# DRV8701E.net
KiCad netlist of a schematic drawn in Altium Designer
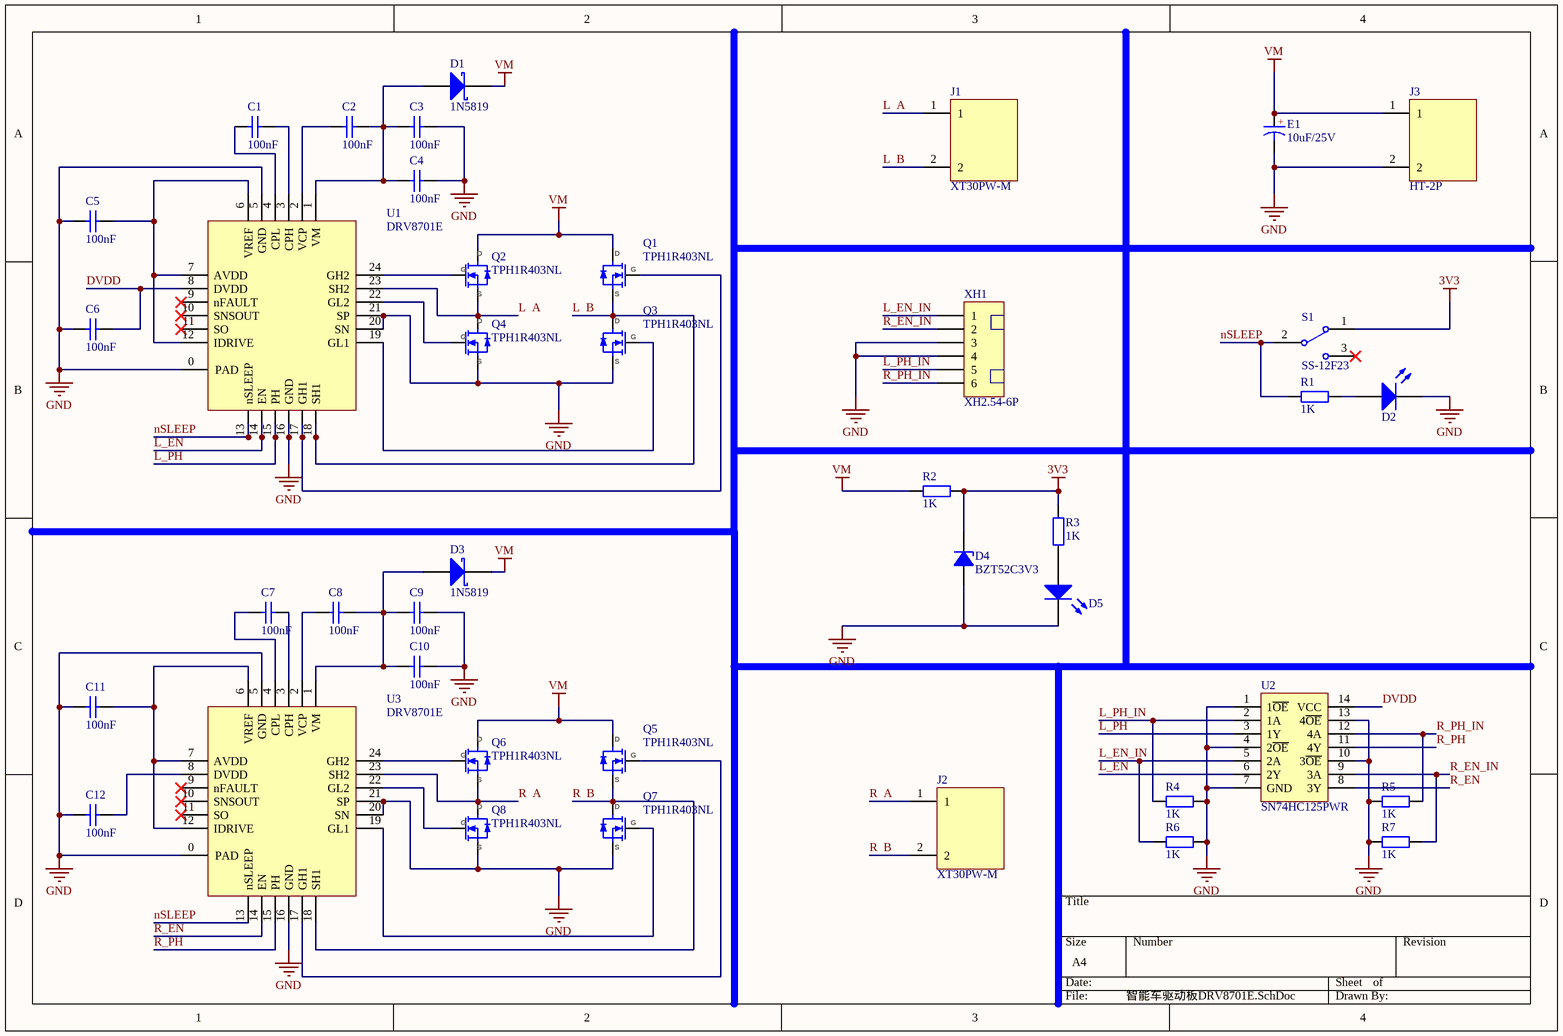
[diagram p0: 智能车驱动板DRV8701E.SchDoc]

(export (version "E")
  (design (tool "Eeschema 10.0.6"))
  (components
    (comp (ref "C1")
      (value "100nF")
      (footprint "C0603_L")
      (description "贴片电容")
      (libsource (lib "0.1_电容&电感&电阻&保险丝") (part "C-SMD"))
    )
    (comp (ref "C2")
      (value "100nF")
      (footprint "C0603_L")
      (description "贴片电容")
      (libsource (lib "0.1_电容&电感&电阻&保险丝") (part "C-SMD"))
    )
    (comp (ref "C3")
      (value "100nF")
      (footprint "C0603_L")
      (description "贴片电容")
      (libsource (lib "0.1_电容&电感&电阻&保险丝") (part "C-SMD"))
    )
    (comp (ref "C4")
      (value "100nF")
      (footprint "C0603_L")
      (description "贴片电容")
      (libsource (lib "0.1_电容&电感&电阻&保险丝") (part "C-SMD"))
    )
    (comp (ref "C5")
      (value "100nF")
      (footprint "C0603_L")
      (description "贴片电容")
      (libsource (lib "0.1_电容&电感&电阻&保险丝") (part "C-SMD"))
    )
    (comp (ref "C6")
      (value "100nF")
      (footprint "C0603_L")
      (description "贴片电容")
      (libsource (lib "0.1_电容&电感&电阻&保险丝") (part "C-SMD"))
    )
    (comp (ref "C7")
      (value "100nF")
      (footprint "C0603_L")
      (description "贴片电容")
      (libsource (lib "0.1_电容&电感&电阻&保险丝") (part "C-SMD"))
    )
    (comp (ref "C8")
      (value "100nF")
      (footprint "C0603_L")
      (description "贴片电容")
      (libsource (lib "0.1_电容&电感&电阻&保险丝") (part "C-SMD"))
    )
    (comp (ref "C9")
      (value "100nF")
      (footprint "C0603_L")
      (description "贴片电容")
      (libsource (lib "0.1_电容&电感&电阻&保险丝") (part "C-SMD"))
    )
    (comp (ref "C10")
      (value "100nF")
      (footprint "C0603_L")
      (description "贴片电容")
      (libsource (lib "0.1_电容&电感&电阻&保险丝") (part "C-SMD"))
    )
    (comp (ref "C11")
      (value "100nF")
      (footprint "C0603_L")
      (description "贴片电容")
      (libsource (lib "0.1_电容&电感&电阻&保险丝") (part "C-SMD"))
    )
    (comp (ref "C12")
      (value "100nF")
      (footprint "C0603_L")
      (description "贴片电容")
      (libsource (lib "0.1_电容&电感&电阻&保险丝") (part "C-SMD"))
    )
    (comp (ref "D1")
      (value "1N5819")
      (footprint "SOD-323")
      (description "肖特基二极管")
      (libsource (lib "0.2_二极管&整流桥") (part "1N5819"))
    )
    (comp (ref "D2")
      (value "LED")
      (footprint "LED-0603_R")
      (description "贴片发光二极管")
      (libsource (lib "0.3_LED发光二极管") (part "LED_SMD"))
    )
    (comp (ref "D3")
      (value "1N5819")
      (footprint "SOD-323")
      (description "肖特基二极管")
      (libsource (lib "0.2_二极管&整流桥") (part "1N5819"))
    )
    (comp (ref "D4")
      (value "BZT52C3V3")
      (footprint "SOD-123-L")
      (description "3.3V稳压二极管")
      (fields (field (name "PUBLISHER") "Altium Limited"))
      (libsource (lib "0.2_二极管&整流桥") (part "Diode Zen"))
    )
    (comp (ref "D5")
      (value "LED")
      (footprint "LED-0603_R")
      (description "贴片发光二极管")
      (libsource (lib "0.3_LED发光二极管") (part "LED_SMD"))
    )
    (comp (ref "E1")
      (value "10uF/25V")
      (footprint "CT-2.0*5*8-R")
      (description "直插固态电容")
      (libsource (lib "0.1_电容&电感&电阻&保险丝") (part "C-CS"))
    )
    (comp (ref "J1")
      (value "XT30PW-M")
      (footprint "XT30-WI")
      (description "30A Low Temperature Rise Fire Retardant Plug")
      (libsource (lib "5.12_XT30&XT60") (part "XT30PW-M"))
    )
    (comp (ref "J2")
      (value "XT30PW-M")
      (footprint "XT30-WI")
      (description "30A Low Temperature Rise Fire Retardant Plug")
      (libsource (lib "5.12_XT30&XT60") (part "XT30PW-M"))
    )
    (comp (ref "J3")
      (value "HT-2P")
      (footprint "CZ-5.08-L-Z-2P")
      (description "30A Low Temperature Rise Fire Retardant Plug")
      (fields (field (name "MANUFACTURER_PART_NUMBER") "XT30PW-M"))
      (libsource (lib "5.12_XT30&XT60") (part "XT30PW-M"))
    )
    (comp (ref "Q1")
      (value "TPH1R403NL")
      (footprint "DFN5x6")
      (description "N沟道MOS")
      (libsource (lib "0.4_场效应管&可控硅") (part "TPH1R403NL"))
    )
    (comp (ref "Q2")
      (value "TPH1R403NL")
      (footprint "DFN5x6")
      (description "N沟道MOS")
      (libsource (lib "0.4_场效应管&可控硅") (part "TPH1R403NL"))
    )
    (comp (ref "Q3")
      (value "TPH1R403NL")
      (footprint "DFN5x6")
      (description "N沟道MOS")
      (libsource (lib "0.4_场效应管&可控硅") (part "TPH1R403NL"))
    )
    (comp (ref "Q4")
      (value "TPH1R403NL")
      (footprint "DFN5x6")
      (description "N沟道MOS")
      (libsource (lib "0.4_场效应管&可控硅") (part "TPH1R403NL"))
    )
    (comp (ref "Q5")
      (value "TPH1R403NL")
      (footprint "DFN5x6")
      (description "N沟道MOS")
      (libsource (lib "0.4_场效应管&可控硅") (part "TPH1R403NL"))
    )
    (comp (ref "Q6")
      (value "TPH1R403NL")
      (footprint "DFN5x6")
      (description "N沟道MOS")
      (libsource (lib "0.4_场效应管&可控硅") (part "TPH1R403NL"))
    )
    (comp (ref "Q7")
      (value "TPH1R403NL")
      (footprint "DFN5x6")
      (description "N沟道MOS")
      (libsource (lib "0.4_场效应管&可控硅") (part "TPH1R403NL"))
    )
    (comp (ref "Q8")
      (value "TPH1R403NL")
      (footprint "DFN5x6")
      (description "N沟道MOS")
      (libsource (lib "0.4_场效应管&可控硅") (part "TPH1R403NL"))
    )
    (comp (ref "R1")
      (value "1K")
      (footprint "R0603_L")
      (description "贴片电阻")
      (libsource (lib "0.1_电容&电感&电阻&保险丝") (part "R-SMD"))
    )
    (comp (ref "R2")
      (value "1K")
      (footprint "R0603_L")
      (description "贴片电阻")
      (libsource (lib "0.1_电容&电感&电阻&保险丝") (part "R-SMD"))
    )
    (comp (ref "R3")
      (value "1K")
      (footprint "R0603_L")
      (description "贴片电阻")
      (libsource (lib "0.1_电容&电感&电阻&保险丝") (part "R-SMD"))
    )
    (comp (ref "R4")
      (value "1K")
      (footprint "R0603_L")
      (description "贴片电阻")
      (libsource (lib "0.1_电容&电感&电阻&保险丝") (part "R-SMD"))
    )
    (comp (ref "R5")
      (value "1K")
      (footprint "R0603_L")
      (description "贴片电阻")
      (libsource (lib "0.1_电容&电感&电阻&保险丝") (part "R-SMD"))
    )
    (comp (ref "R6")
      (value "1K")
      (footprint "R0603_L")
      (description "贴片电阻")
      (libsource (lib "0.1_电容&电感&电阻&保险丝") (part "R-SMD"))
    )
    (comp (ref "R7")
      (value "1K")
      (footprint "R0603_L")
      (description "贴片电阻")
      (libsource (lib "0.1_电容&电感&电阻&保险丝") (part "R-SMD"))
    )
    (comp (ref "S1")
      (value "SS-12F23")
      (footprint "SS-12D10")
      (description "1路波动开关")
      (libsource (lib "0.8_按键&开关") (part "SSW-1P"))
    )
    (comp (ref "U1")
      (value "DRV8701E")
      (footprint "QFN24-4x4")
      (description "DRV8701E Ti全桥驱动芯片")
      (libsource (lib "1.3_电机驱动芯片") (part "DRV8701E"))
    )
    (comp (ref "U2")
      (value "SN74HC125PWR")
      (footprint "TSSOP14")
      (description "三态输出的四路缓冲器")
      (libsource (lib "1.7_隔离类芯片") (part "SN74HC125PWR"))
    )
    (comp (ref "U3")
      (value "DRV8701E")
      (footprint "QFN24-4x4")
      (description "DRV8701E Ti全桥驱动芯片")
      (libsource (lib "1.3_电机驱动芯片") (part "DRV8701E"))
    )
    (comp (ref "XH1")
      (value "XH2.54-6P")
      (footprint "XH2.54-6P-WI")
      (libsource (lib "5.2_XH") (part "XH2.54-6P"))
    )
  )
  (nets
    (net (code "1") (name "/DVDD") (class "Default")
      (node (ref "C6") (pin "2") (pinfunction "2_2") (pintype "passive"))
      (node (ref "U1") (pin "8") (pinfunction "DVDD_8") (pintype "passive"))
      (node (ref "U2") (pin "14") (pinfunction "VCC_14") (pintype "passive"))
    )
    (net (code "2") (name "/L  A") (class "Default")
      (node (ref "J1") (pin "1") (pinfunction "1_1") (pintype "passive"))
      (node (ref "Q2") (pin "3") (pinfunction "S_3") (pintype "passive"))
      (node (ref "Q4") (pin "1") (pinfunction "D_1") (pintype "passive"))
      (node (ref "U1") (pin "23") (pinfunction "SH2_23") (pintype "passive"))
    )
    (net (code "3") (name "/L  B") (class "Default")
      (node (ref "J1") (pin "2") (pinfunction "2_2") (pintype "passive"))
      (node (ref "Q1") (pin "3") (pinfunction "S_3") (pintype "passive"))
      (node (ref "Q3") (pin "1") (pinfunction "D_1") (pintype "passive"))
      (node (ref "U1") (pin "18") (pinfunction "SH1_18") (pintype "passive"))
    )
    (net (code "4") (name "/L_EN") (class "Default")
      (node (ref "U1") (pin "14") (pinfunction "EN_14") (pintype "passive"))
      (node (ref "U2") (pin "6") (pinfunction "2Y_6") (pintype "passive"))
    )
    (net (code "5") (name "/L_EN_IN") (class "Default")
      (node (ref "R6") (pin "1") (pinfunction "1_1") (pintype "passive"))
      (node (ref "U2") (pin "5") (pinfunction "2A_5") (pintype "passive"))
      (node (ref "XH1") (pin "1") (pinfunction "1_1") (pintype "passive"))
    )
    (net (code "6") (name "/L_PH") (class "Default")
      (node (ref "U1") (pin "15") (pinfunction "PH_15") (pintype "passive"))
      (node (ref "U2") (pin "3") (pinfunction "1Y_3") (pintype "passive"))
    )
    (net (code "7") (name "/L_PH_IN") (class "Default")
      (node (ref "R4") (pin "1") (pinfunction "1_1") (pintype "passive"))
      (node (ref "U2") (pin "2") (pinfunction "1A_2") (pintype "passive"))
      (node (ref "XH1") (pin "5") (pinfunction "5_5") (pintype "passive"))
    )
    (net (code "8") (name "/R  A") (class "Default")
      (node (ref "J2") (pin "1") (pinfunction "1_1") (pintype "passive"))
      (node (ref "Q6") (pin "3") (pinfunction "S_3") (pintype "passive"))
      (node (ref "Q8") (pin "1") (pinfunction "D_1") (pintype "passive"))
      (node (ref "U3") (pin "23") (pinfunction "SH2_23") (pintype "passive"))
    )
    (net (code "9") (name "/R  B") (class "Default")
      (node (ref "J2") (pin "2") (pinfunction "2_2") (pintype "passive"))
      (node (ref "Q5") (pin "3") (pinfunction "S_3") (pintype "passive"))
      (node (ref "Q7") (pin "1") (pinfunction "D_1") (pintype "passive"))
      (node (ref "U3") (pin "18") (pinfunction "SH1_18") (pintype "passive"))
    )
    (net (code "10") (name "/R_EN") (class "Default")
      (node (ref "U2") (pin "8") (pinfunction "3Y_8") (pintype "passive"))
      (node (ref "U3") (pin "14") (pinfunction "EN_14") (pintype "passive"))
    )
    (net (code "11") (name "/R_EN_IN") (class "Default")
      (node (ref "R7") (pin "2") (pinfunction "2_2") (pintype "passive"))
      (node (ref "U2") (pin "9") (pinfunction "3A_9") (pintype "passive"))
      (node (ref "XH1") (pin "2") (pinfunction "2_2") (pintype "passive"))
    )
    (net (code "12") (name "/R_PH") (class "Default")
      (node (ref "U2") (pin "11") (pinfunction "4Y_11") (pintype "passive"))
      (node (ref "U3") (pin "15") (pinfunction "PH_15") (pintype "passive"))
    )
    (net (code "13") (name "/R_PH_IN") (class "Default")
      (node (ref "R5") (pin "2") (pinfunction "2_2") (pintype "passive"))
      (node (ref "U2") (pin "12") (pinfunction "4A_12") (pintype "passive"))
      (node (ref "XH1") (pin "6") (pinfunction "6_6") (pintype "passive"))
    )
    (net (code "14") (name "/nSLEEP") (class "Default")
      (node (ref "R1") (pin "1") (pinfunction "1_1") (pintype "passive"))
      (node (ref "S1") (pin "2") (pinfunction "2_2") (pintype "passive"))
      (node (ref "U1") (pin "13") (pinfunction "nSLEEP_13") (pintype "passive"))
      (node (ref "U3") (pin "13") (pinfunction "nSLEEP_13") (pintype "passive"))
    )
    (net (code "15") (name "3V3") (class "Default")
      (node (ref "D4") (pin "K") (pinfunction "K_K") (pintype "passive"))
      (node (ref "R2") (pin "2") (pinfunction "2_2") (pintype "passive"))
      (node (ref "R3") (pin "2") (pinfunction "2_2") (pintype "passive"))
      (node (ref "S1") (pin "1") (pinfunction "1_1") (pintype "passive"))
    )
    (net (code "16") (name "GND") (class "Default")
      (node (ref "C10") (pin "2") (pinfunction "2_2") (pintype "passive"))
      (node (ref "C11") (pin "1") (pinfunction "1_1") (pintype "passive"))
      (node (ref "C12") (pin "1") (pinfunction "1_1") (pintype "passive"))
      (node (ref "C3") (pin "2") (pinfunction "2_2") (pintype "passive"))
      (node (ref "C4") (pin "2") (pinfunction "2_2") (pintype "passive"))
      (node (ref "C5") (pin "1") (pinfunction "1_1") (pintype "passive"))
      (node (ref "C6") (pin "1") (pinfunction "1_1") (pintype "passive"))
      (node (ref "C9") (pin "2") (pinfunction "2_2") (pintype "passive"))
      (node (ref "D2") (pin "2") (pinfunction "K_2") (pintype "passive"))
      (node (ref "D4") (pin "A") (pinfunction "A_A") (pintype "passive"))
      (node (ref "D5") (pin "2") (pinfunction "K_2") (pintype "passive"))
      (node (ref "E1") (pin "2") (pinfunction "2_2") (pintype "passive"))
      (node (ref "J3") (pin "2") (pinfunction "2_2") (pintype "passive"))
      (node (ref "Q3") (pin "3") (pinfunction "S_3") (pintype "passive"))
      (node (ref "Q4") (pin "3") (pinfunction "S_3") (pintype "passive"))
      (node (ref "Q7") (pin "3") (pinfunction "S_3") (pintype "passive"))
      (node (ref "Q8") (pin "3") (pinfunction "S_3") (pintype "passive"))
      (node (ref "R4") (pin "2") (pinfunction "2_2") (pintype "passive"))
      (node (ref "R5") (pin "1") (pinfunction "1_1") (pintype "passive"))
      (node (ref "R6") (pin "2") (pinfunction "2_2") (pintype "passive"))
      (node (ref "R7") (pin "1") (pinfunction "1_1") (pintype "passive"))
      (node (ref "U1") (pin "0") (pinfunction "PAD_0") (pintype "passive"))
      (node (ref "U1") (pin "16") (pinfunction "GND_16") (pintype "passive"))
      (node (ref "U1") (pin "20") (pinfunction "SN_20") (pintype "passive"))
      (node (ref "U1") (pin "21") (pinfunction "SP_21") (pintype "passive"))
      (node (ref "U1") (pin "5") (pinfunction "GND_5") (pintype "passive"))
      (node (ref "U2") (pin "1") (pinfunction "1~{OE}_1") (pintype "passive"))
      (node (ref "U2") (pin "10") (pinfunction "3~{OE}_10") (pintype "passive"))
      (node (ref "U2") (pin "13") (pinfunction "4~{OE}_13") (pintype "passive"))
      (node (ref "U2") (pin "4") (pinfunction "2~{OE}_4") (pintype "passive"))
      (node (ref "U2") (pin "7") (pinfunction "GND_7") (pintype "passive"))
      (node (ref "U3") (pin "0") (pinfunction "PAD_0") (pintype "passive"))
      (node (ref "U3") (pin "16") (pinfunction "GND_16") (pintype "passive"))
      (node (ref "U3") (pin "20") (pinfunction "SN_20") (pintype "passive"))
      (node (ref "U3") (pin "21") (pinfunction "SP_21") (pintype "passive"))
      (node (ref "U3") (pin "5") (pinfunction "GND_5") (pintype "passive"))
      (node (ref "XH1") (pin "3") (pinfunction "3_3") (pintype "passive"))
      (node (ref "XH1") (pin "4") (pinfunction "4_4") (pintype "passive"))
    )
    (net (code "17") (name "Net-(D1-A)") (class "Default")
      (node (ref "C2") (pin "2") (pinfunction "2_2") (pintype "passive"))
      (node (ref "C3") (pin "1") (pinfunction "1_1") (pintype "passive"))
      (node (ref "C4") (pin "1") (pinfunction "1_1") (pintype "passive"))
      (node (ref "D1") (pin "1") (pinfunction "A_1") (pintype "passive"))
      (node (ref "U1") (pin "1") (pinfunction "VM_1") (pintype "passive"))
    )
    (net (code "18") (name "Net-(D2-A)") (class "Default")
      (node (ref "D2") (pin "1") (pinfunction "A_1") (pintype "passive"))
      (node (ref "R1") (pin "2") (pinfunction "2_2") (pintype "passive"))
    )
    (net (code "19") (name "Net-(D3-A)") (class "Default")
      (node (ref "C10") (pin "1") (pinfunction "1_1") (pintype "passive"))
      (node (ref "C8") (pin "2") (pinfunction "2_2") (pintype "passive"))
      (node (ref "C9") (pin "1") (pinfunction "1_1") (pintype "passive"))
      (node (ref "D3") (pin "1") (pinfunction "A_1") (pintype "passive"))
      (node (ref "U3") (pin "1") (pinfunction "VM_1") (pintype "passive"))
    )
    (net (code "20") (name "Net-(D5-A)") (class "Default")
      (node (ref "D5") (pin "1") (pinfunction "A_1") (pintype "passive"))
      (node (ref "R3") (pin "1") (pinfunction "1_1") (pintype "passive"))
    )
    (net (code "21") (name "Net-(Q1-G)") (class "Default")
      (node (ref "Q1") (pin "2") (pinfunction "G_2") (pintype "passive"))
      (node (ref "U1") (pin "17") (pinfunction "GH1_17") (pintype "passive"))
    )
    (net (code "22") (name "Net-(Q2-G)") (class "Default")
      (node (ref "Q2") (pin "2") (pinfunction "G_2") (pintype "passive"))
      (node (ref "U1") (pin "24") (pinfunction "GH2_24") (pintype "passive"))
    )
    (net (code "23") (name "Net-(Q3-G)") (class "Default")
      (node (ref "Q3") (pin "2") (pinfunction "G_2") (pintype "passive"))
      (node (ref "U1") (pin "19") (pinfunction "GL1_19") (pintype "passive"))
    )
    (net (code "24") (name "Net-(Q4-G)") (class "Default")
      (node (ref "Q4") (pin "2") (pinfunction "G_2") (pintype "passive"))
      (node (ref "U1") (pin "22") (pinfunction "GL2_22") (pintype "passive"))
    )
    (net (code "25") (name "Net-(Q5-G)") (class "Default")
      (node (ref "Q5") (pin "2") (pinfunction "G_2") (pintype "passive"))
      (node (ref "U3") (pin "17") (pinfunction "GH1_17") (pintype "passive"))
    )
    (net (code "26") (name "Net-(Q6-G)") (class "Default")
      (node (ref "Q6") (pin "2") (pinfunction "G_2") (pintype "passive"))
      (node (ref "U3") (pin "24") (pinfunction "GH2_24") (pintype "passive"))
    )
    (net (code "27") (name "Net-(Q7-G)") (class "Default")
      (node (ref "Q7") (pin "2") (pinfunction "G_2") (pintype "passive"))
      (node (ref "U3") (pin "19") (pinfunction "GL1_19") (pintype "passive"))
    )
    (net (code "28") (name "Net-(Q8-G)") (class "Default")
      (node (ref "Q8") (pin "2") (pinfunction "G_2") (pintype "passive"))
      (node (ref "U3") (pin "22") (pinfunction "GL2_22") (pintype "passive"))
    )
    (net (code "29") (name "Net-(U1-AVDD)") (class "Default")
      (node (ref "C5") (pin "2") (pinfunction "2_2") (pintype "passive"))
      (node (ref "U1") (pin "12") (pinfunction "IDRIVE_12") (pintype "passive"))
      (node (ref "U1") (pin "6") (pinfunction "VREF_6") (pintype "passive"))
      (node (ref "U1") (pin "7") (pinfunction "AVDD_7") (pintype "passive"))
    )
    (net (code "30") (name "Net-(U1-CPH)") (class "Default")
      (node (ref "C1") (pin "2") (pinfunction "2_2") (pintype "passive"))
      (node (ref "U1") (pin "3") (pinfunction "CPH_3") (pintype "passive"))
    )
    (net (code "31") (name "Net-(U1-CPL)") (class "Default")
      (node (ref "C1") (pin "1") (pinfunction "1_1") (pintype "passive"))
      (node (ref "U1") (pin "4") (pinfunction "CPL_4") (pintype "passive"))
    )
    (net (code "32") (name "Net-(U1-VCP)") (class "Default")
      (node (ref "C2") (pin "1") (pinfunction "1_1") (pintype "passive"))
      (node (ref "U1") (pin "2") (pinfunction "VCP_2") (pintype "passive"))
    )
    (net (code "33") (name "Net-(U3-AVDD)") (class "Default")
      (node (ref "C11") (pin "2") (pinfunction "2_2") (pintype "passive"))
      (node (ref "U3") (pin "12") (pinfunction "IDRIVE_12") (pintype "passive"))
      (node (ref "U3") (pin "6") (pinfunction "VREF_6") (pintype "passive"))
      (node (ref "U3") (pin "7") (pinfunction "AVDD_7") (pintype "passive"))
    )
    (net (code "34") (name "Net-(U3-CPH)") (class "Default")
      (node (ref "C7") (pin "2") (pinfunction "2_2") (pintype "passive"))
      (node (ref "U3") (pin "3") (pinfunction "CPH_3") (pintype "passive"))
    )
    (net (code "35") (name "Net-(U3-CPL)") (class "Default")
      (node (ref "C7") (pin "1") (pinfunction "1_1") (pintype "passive"))
      (node (ref "U3") (pin "4") (pinfunction "CPL_4") (pintype "passive"))
    )
    (net (code "36") (name "Net-(U3-DVDD)") (class "Default")
      (node (ref "C12") (pin "2") (pinfunction "2_2") (pintype "passive"))
      (node (ref "U3") (pin "8") (pinfunction "DVDD_8") (pintype "passive"))
    )
    (net (code "37") (name "Net-(U3-VCP)") (class "Default")
      (node (ref "C8") (pin "1") (pinfunction "1_1") (pintype "passive"))
      (node (ref "U3") (pin "2") (pinfunction "VCP_2") (pintype "passive"))
    )
    (net (code "38") (name "VM") (class "Default")
      (node (ref "D1") (pin "2") (pinfunction "K_2") (pintype "passive"))
      (node (ref "D3") (pin "2") (pinfunction "K_2") (pintype "passive"))
      (node (ref "E1") (pin "1") (pinfunction "1_1") (pintype "passive"))
      (node (ref "J3") (pin "1") (pinfunction "1_1") (pintype "passive"))
      (node (ref "Q1") (pin "1") (pinfunction "D_1") (pintype "passive"))
      (node (ref "Q2") (pin "1") (pinfunction "D_1") (pintype "passive"))
      (node (ref "Q5") (pin "1") (pinfunction "D_1") (pintype "passive"))
      (node (ref "Q6") (pin "1") (pinfunction "D_1") (pintype "passive"))
      (node (ref "R2") (pin "1") (pinfunction "1_1") (pintype "passive"))
    )
    (net (code "39") (name "unconnected-(S1-Pad3)") (class "Default")
      (node (ref "S1") (pin "3") (pinfunction "3_3") (pintype "passive+no_connect"))
    )
    (net (code "40") (name "unconnected-(U1-SNSOUT-Pad10)") (class "Default")
      (node (ref "U1") (pin "10") (pinfunction "SNSOUT_10") (pintype "passive+no_connect"))
    )
    (net (code "41") (name "unconnected-(U1-SO-Pad11)") (class "Default")
      (node (ref "U1") (pin "11") (pinfunction "SO_11") (pintype "passive+no_connect"))
    )
    (net (code "42") (name "unconnected-(U1-nFAULT-Pad9)") (class "Default")
      (node (ref "U1") (pin "9") (pinfunction "nFAULT_9") (pintype "passive+no_connect"))
    )
    (net (code "43") (name "unconnected-(U3-SNSOUT-Pad10)") (class "Default")
      (node (ref "U3") (pin "10") (pinfunction "SNSOUT_10") (pintype "passive+no_connect"))
    )
    (net (code "44") (name "unconnected-(U3-SO-Pad11)") (class "Default")
      (node (ref "U3") (pin "11") (pinfunction "SO_11") (pintype "passive+no_connect"))
    )
    (net (code "45") (name "unconnected-(U3-nFAULT-Pad9)") (class "Default")
      (node (ref "U3") (pin "9") (pinfunction "nFAULT_9") (pintype "passive+no_connect"))
    )
  )
)
